# Digital_Port_C_Default_State_DIP.net
KiCad netlist of a schematic drawn in Altium Designer
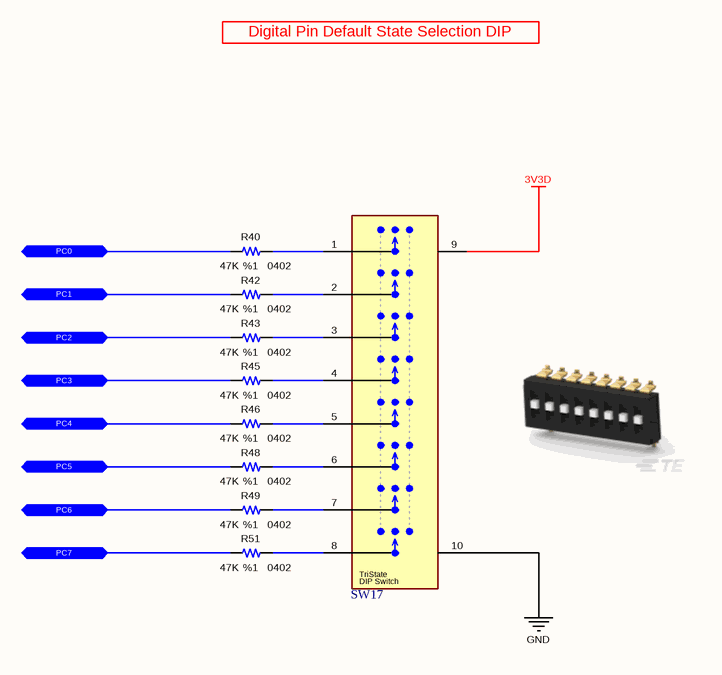
[diagram p0: Digital Port C Default State DIP.SchDoc]

(export (version "E")
  (design (tool "Eeschema 10.0.6"))
  (components
    (comp (ref "R40")
      (value "47K")
      (footprint "RESISTOR_0402")
      (description "Thick Film Resistors - SMD 1/16 W 47 Kohms 1%")
      (fields
        (field (name "MANUFACTURER PART NUMBER") "CRCW040247K0FKED")
        (field (name "MOUSER PART NUMBER") "71-CRCW0402-47K-E3")
        (field (name "TOLERANCE") "%1")
        (field (name "CASE") "0402")
      )
      (libsource (lib "Ovoo_Library") (part "Resistor - 47K"))
    )
    (comp (ref "R42")
      (value "47K")
      (footprint "RESISTOR_0402")
      (description "Thick Film Resistors - SMD 1/16 W 47 Kohms 1%")
      (fields
        (field (name "MANUFACTURER PART NUMBER") "CRCW040247K0FKED")
        (field (name "MOUSER PART NUMBER") "71-CRCW0402-47K-E3")
        (field (name "TOLERANCE") "%1")
        (field (name "CASE") "0402")
      )
      (libsource (lib "Ovoo_Library") (part "Resistor - 47K"))
    )
    (comp (ref "R43")
      (value "47K")
      (footprint "RESISTOR_0402")
      (description "Thick Film Resistors - SMD 1/16 W 47 Kohms 1%")
      (fields
        (field (name "MANUFACTURER PART NUMBER") "CRCW040247K0FKED")
        (field (name "MOUSER PART NUMBER") "71-CRCW0402-47K-E3")
        (field (name "TOLERANCE") "%1")
        (field (name "CASE") "0402")
      )
      (libsource (lib "Ovoo_Library") (part "Resistor - 47K"))
    )
    (comp (ref "R45")
      (value "47K")
      (footprint "RESISTOR_0402")
      (description "Thick Film Resistors - SMD 1/16 W 47 Kohms 1%")
      (fields
        (field (name "MANUFACTURER PART NUMBER") "CRCW040247K0FKED")
        (field (name "MOUSER PART NUMBER") "71-CRCW0402-47K-E3")
        (field (name "TOLERANCE") "%1")
        (field (name "CASE") "0402")
      )
      (libsource (lib "Ovoo_Library") (part "Resistor - 47K"))
    )
    (comp (ref "R46")
      (value "47K")
      (footprint "RESISTOR_0402")
      (description "Thick Film Resistors - SMD 1/16 W 47 Kohms 1%")
      (fields
        (field (name "MANUFACTURER PART NUMBER") "CRCW040247K0FKED")
        (field (name "MOUSER PART NUMBER") "71-CRCW0402-47K-E3")
        (field (name "TOLERANCE") "%1")
        (field (name "CASE") "0402")
      )
      (libsource (lib "Ovoo_Library") (part "Resistor - 47K"))
    )
    (comp (ref "R48")
      (value "47K")
      (footprint "RESISTOR_0402")
      (description "Thick Film Resistors - SMD 1/16 W 47 Kohms 1%")
      (fields
        (field (name "MANUFACTURER PART NUMBER") "CRCW040247K0FKED")
        (field (name "MOUSER PART NUMBER") "71-CRCW0402-47K-E3")
        (field (name "TOLERANCE") "%1")
        (field (name "CASE") "0402")
      )
      (libsource (lib "Ovoo_Library") (part "Resistor - 47K"))
    )
    (comp (ref "R49")
      (value "47K")
      (footprint "RESISTOR_0402")
      (description "Thick Film Resistors - SMD 1/16 W 47 Kohms 1%")
      (fields
        (field (name "MANUFACTURER PART NUMBER") "CRCW040247K0FKED")
        (field (name "MOUSER PART NUMBER") "71-CRCW0402-47K-E3")
        (field (name "TOLERANCE") "%1")
        (field (name "CASE") "0402")
      )
      (libsource (lib "Ovoo_Library") (part "Resistor - 47K"))
    )
    (comp (ref "R51")
      (value "47K")
      (footprint "RESISTOR_0402")
      (description "Thick Film Resistors - SMD 1/16 W 47 Kohms 1%")
      (fields
        (field (name "MANUFACTURER PART NUMBER") "CRCW040247K0FKED")
        (field (name "MOUSER PART NUMBER") "71-CRCW0402-47K-E3")
        (field (name "TOLERANCE") "%1")
        (field (name "CASE") "0402")
      )
      (libsource (lib "Ovoo_Library") (part "Resistor - 47K"))
    )
    (comp (ref "SW17")
      (value "DIP Switches/SIP Switches")
      (footprint "TDS08SGNNTR04")
      (description "DIP Switches/SIP Switches TRI-STATE DIP 8P G RAISED T&R")
      (fields
        (field (name "MANUFACTURER PART NUMBER") "TDS08SGNNTR04")
        (field (name "MOUSER PART NUMBER") "506-TDS08SGNNTR04")
      )
      (libsource (lib "Ovoo_Library") (part "Switch - DIP Switch (8 Pole TriState)"))
    )
  )
  (nets
    (net (code "1") (name "/PC0") (class "Default")
      (node (ref "R40") (pin "2") (pinfunction "2_2") (pintype "passive"))
    )
    (net (code "2") (name "/PC1") (class "Default")
      (node (ref "R42") (pin "2") (pinfunction "2_2") (pintype "passive"))
    )
    (net (code "3") (name "/PC2") (class "Default")
      (node (ref "R43") (pin "2") (pinfunction "2_2") (pintype "passive"))
    )
    (net (code "4") (name "/PC3") (class "Default")
      (node (ref "R45") (pin "2") (pinfunction "2_2") (pintype "passive"))
    )
    (net (code "5") (name "/PC4") (class "Default")
      (node (ref "R46") (pin "2") (pinfunction "2_2") (pintype "passive"))
    )
    (net (code "6") (name "/PC5") (class "Default")
      (node (ref "R48") (pin "2") (pinfunction "2_2") (pintype "passive"))
    )
    (net (code "7") (name "/PC6") (class "Default")
      (node (ref "R49") (pin "2") (pinfunction "2_2") (pintype "passive"))
    )
    (net (code "8") (name "/PC7") (class "Default")
      (node (ref "R51") (pin "2") (pinfunction "2_2") (pintype "passive"))
    )
    (net (code "9") (name "3V3D") (class "Default")
      (node (ref "SW17") (pin "9") (pinfunction "VCC_9") (pintype "passive"))
    )
    (net (code "10") (name "GND") (class "Default")
      (node (ref "SW17") (pin "10") (pinfunction "GND_10") (pintype "passive"))
    )
    (net (code "11") (name "Net-(R40-Pad1)") (class "Default")
      (node (ref "R40") (pin "1") (pinfunction "1_1") (pintype "passive"))
      (node (ref "SW17") (pin "1") (pinfunction "1_1") (pintype "passive"))
    )
    (net (code "12") (name "Net-(R42-Pad1)") (class "Default")
      (node (ref "R42") (pin "1") (pinfunction "1_1") (pintype "passive"))
      (node (ref "SW17") (pin "2") (pinfunction "2_2") (pintype "passive"))
    )
    (net (code "13") (name "Net-(R43-Pad1)") (class "Default")
      (node (ref "R43") (pin "1") (pinfunction "1_1") (pintype "passive"))
      (node (ref "SW17") (pin "3") (pinfunction "3_3") (pintype "passive"))
    )
    (net (code "14") (name "Net-(R45-Pad1)") (class "Default")
      (node (ref "R45") (pin "1") (pinfunction "1_1") (pintype "passive"))
      (node (ref "SW17") (pin "4") (pinfunction "4_4") (pintype "passive"))
    )
    (net (code "15") (name "Net-(R46-Pad1)") (class "Default")
      (node (ref "R46") (pin "1") (pinfunction "1_1") (pintype "passive"))
      (node (ref "SW17") (pin "5") (pinfunction "5_5") (pintype "passive"))
    )
    (net (code "16") (name "Net-(R48-Pad1)") (class "Default")
      (node (ref "R48") (pin "1") (pinfunction "1_1") (pintype "passive"))
      (node (ref "SW17") (pin "6") (pinfunction "6_6") (pintype "passive"))
    )
    (net (code "17") (name "Net-(R49-Pad1)") (class "Default")
      (node (ref "R49") (pin "1") (pinfunction "1_1") (pintype "passive"))
      (node (ref "SW17") (pin "7") (pinfunction "7_7") (pintype "passive"))
    )
    (net (code "18") (name "Net-(R51-Pad1)") (class "Default")
      (node (ref "R51") (pin "1") (pinfunction "1_1") (pintype "passive"))
      (node (ref "SW17") (pin "8") (pinfunction "8_8") (pintype "passive"))
    )
  )
)
